# RaspBle.net
KiCad netlist of a schematic drawn in EAGLE
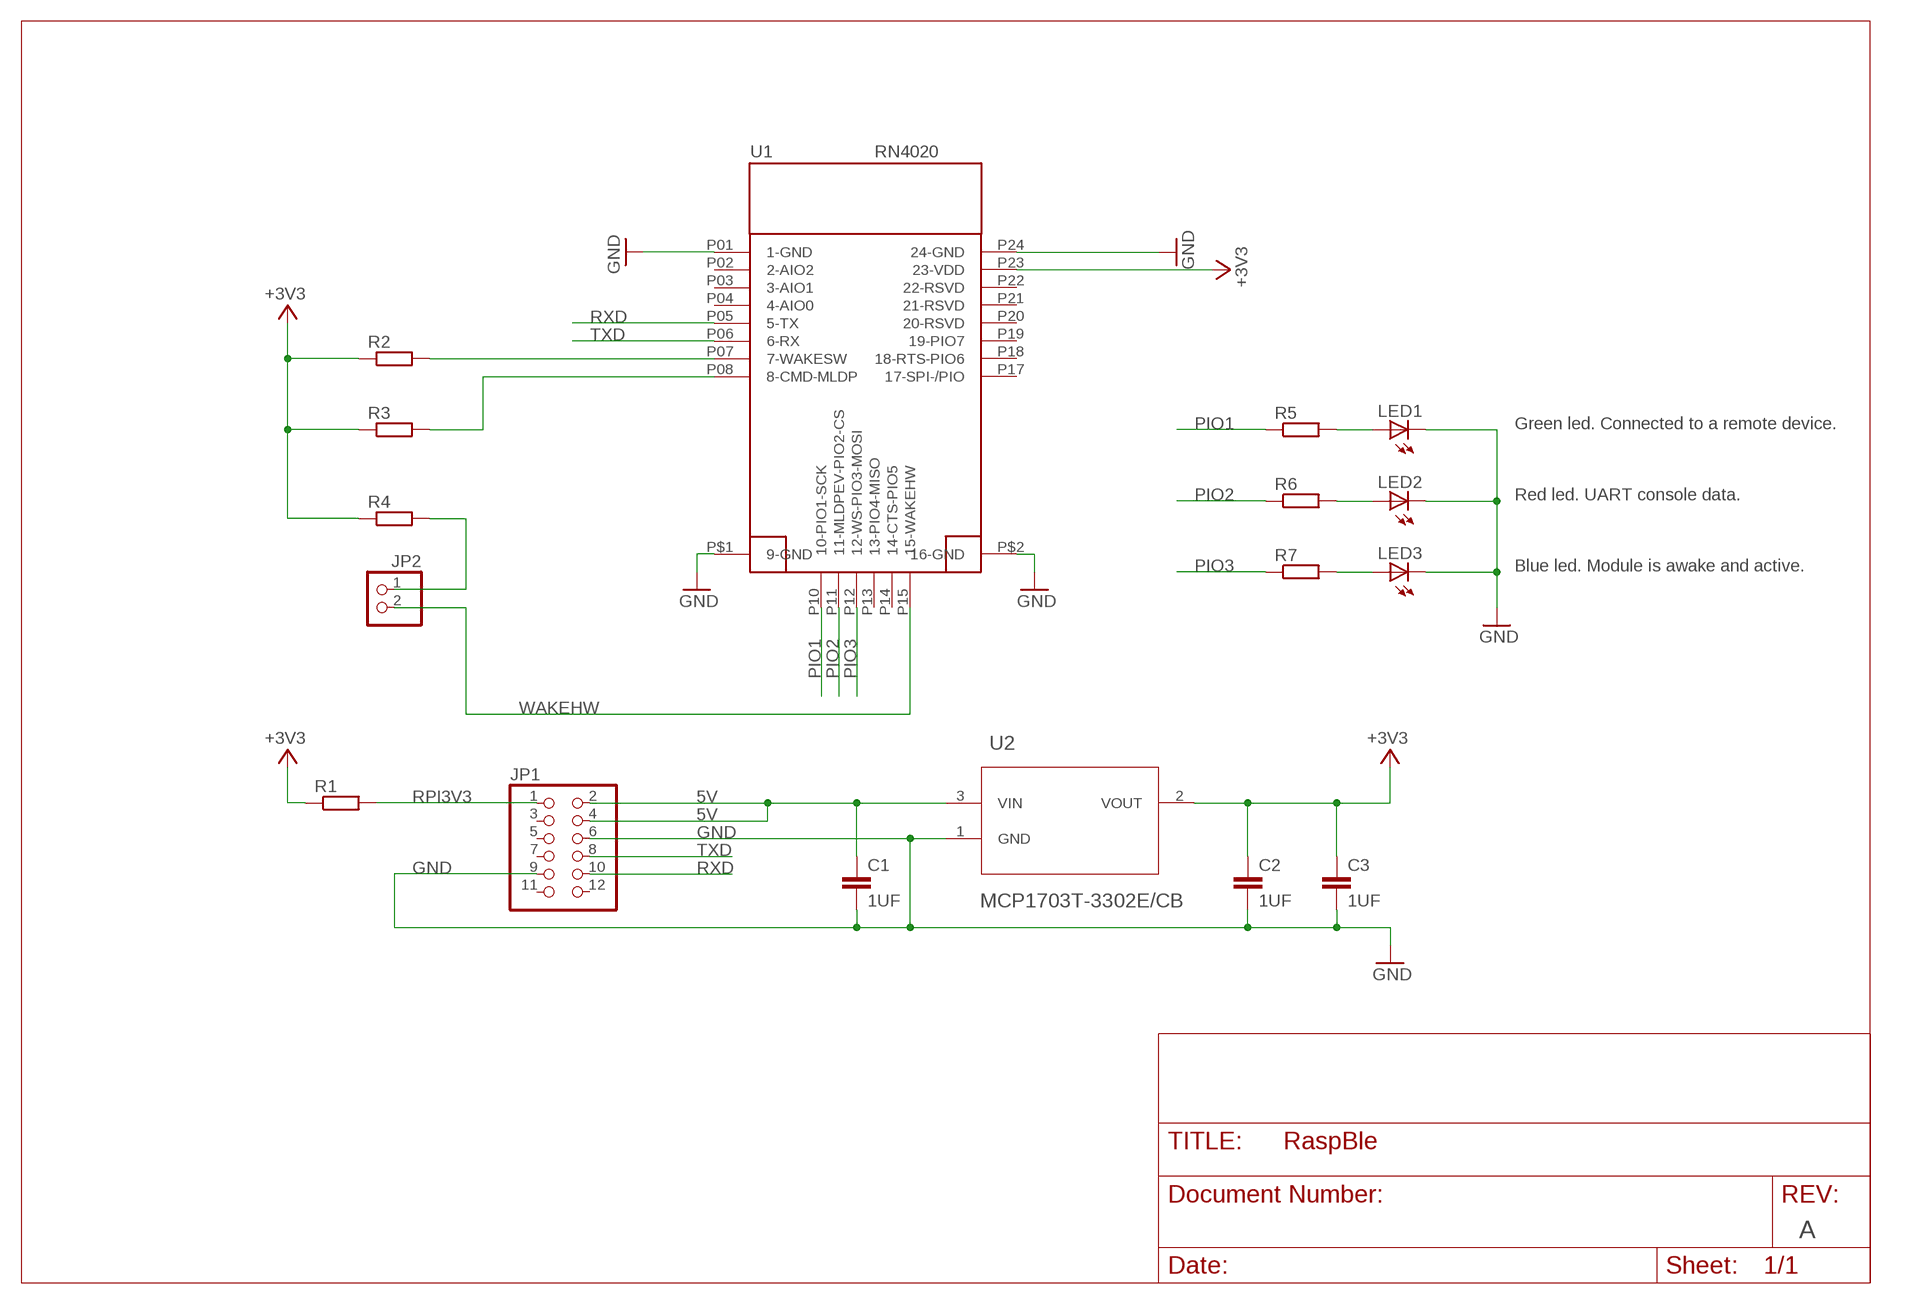
[diagram p0: schematic, sheet 1]

(export (version "E")
  (design (tool "Eeschema 10.0.6"))
  (components
    (comp (ref "C1")
      (value "1UF")
      (footprint "eagle-import:C1206")
      (libsource (lib "eagle-import") (part "C-EUC1206"))
    )
    (comp (ref "C2")
      (value "1UF")
      (footprint "eagle-import:C1206")
      (libsource (lib "eagle-import") (part "C-EUC1206"))
    )
    (comp (ref "C3")
      (value "1UF")
      (footprint "eagle-import:C1206")
      (libsource (lib "eagle-import") (part "C-EUC1206"))
    )
    (comp (ref "JP1")
      (value "PINHD-2X6")
      (footprint "eagle-import:2X06")
      (libsource (lib "eagle-import") (part "PINHD-2X6"))
    )
    (comp (ref "JP2")
      (value "PINHD-1X2")
      (footprint "eagle-import:1X02")
      (libsource (lib "eagle-import") (part "PINHD-1X2"))
    )
    (comp (ref "LED1")
      (value "LEDSML1206")
      (footprint "eagle-import:SML1206")
      (libsource (lib "eagle-import") (part "LEDSML1206"))
    )
    (comp (ref "LED2")
      (value "LEDSML1206")
      (footprint "eagle-import:SML1206")
      (libsource (lib "eagle-import") (part "LEDSML1206"))
    )
    (comp (ref "LED3")
      (value "LEDSML1206")
      (footprint "eagle-import:SML1206")
      (libsource (lib "eagle-import") (part "LEDSML1206"))
    )
    (comp (ref "R1")
      (value "R-EU_R1206")
      (footprint "eagle-import:R1206")
      (libsource (lib "eagle-import") (part "R-EU_R1206"))
    )
    (comp (ref "R2")
      (value "R-EU_R1206")
      (footprint "eagle-import:R1206")
      (libsource (lib "eagle-import") (part "R-EU_R1206"))
    )
    (comp (ref "R3")
      (value "R-EU_R1206")
      (footprint "eagle-import:R1206")
      (libsource (lib "eagle-import") (part "R-EU_R1206"))
    )
    (comp (ref "R4")
      (value "R-EU_R1206")
      (footprint "eagle-import:R1206")
      (libsource (lib "eagle-import") (part "R-EU_R1206"))
    )
    (comp (ref "R5")
      (value "R-EU_R1206")
      (footprint "eagle-import:R1206")
      (libsource (lib "eagle-import") (part "R-EU_R1206"))
    )
    (comp (ref "R6")
      (value "R-EU_R1206")
      (footprint "eagle-import:R1206")
      (libsource (lib "eagle-import") (part "R-EU_R1206"))
    )
    (comp (ref "R7")
      (value "R-EU_R1206")
      (footprint "eagle-import:R1206")
      (libsource (lib "eagle-import") (part "R-EU_R1206"))
    )
    (comp (ref "U1")
      (value "RN4020")
      (footprint "eagle-import:RN4020SMD")
      (libsource (lib "eagle-import") (part "RN4020"))
    )
    (comp (ref "U2")
      (value "MCP1703T-3302E/CB")
      (footprint "eagle-import:SOT95P300X145-3N")
      (libsource (lib "eagle-import") (part "MCP1703T-3302E/CB"))
    )
  )
  (nets
    (net (code "1") (name "+3V3") (class "Default")
      (node (ref "C2") (pin "1") (pinfunction "1_1") (pintype "passive"))
      (node (ref "C3") (pin "1") (pinfunction "1_1") (pintype "passive"))
      (node (ref "R1") (pin "1") (pinfunction "1_1") (pintype "passive"))
      (node (ref "R2") (pin "1") (pinfunction "1_1") (pintype "passive"))
      (node (ref "R3") (pin "1") (pinfunction "1_1") (pintype "passive"))
      (node (ref "R4") (pin "1") (pinfunction "1_1") (pintype "passive"))
      (node (ref "U1") (pin "P23") (pinfunction "23-VDD_P23") (pintype "bidirectional"))
      (node (ref "U2") (pin "2") (pinfunction "VOUT_2") (pintype "output"))
    )
    (net (code "2") (name "/5V") (class "Default")
      (node (ref "C1") (pin "1") (pinfunction "1_1") (pintype "passive"))
      (node (ref "JP1") (pin "2") (pinfunction "2_2") (pintype "passive"))
      (node (ref "JP1") (pin "4") (pinfunction "4_4") (pintype "passive"))
      (node (ref "U2") (pin "3") (pinfunction "VIN_3") (pintype "input"))
    )
    (net (code "3") (name "/PIO1") (class "Default")
      (node (ref "R5") (pin "1") (pinfunction "1_1") (pintype "passive"))
      (node (ref "U1") (pin "P10") (pinfunction "10-PIO1-SCK_P10") (pintype "bidirectional"))
    )
    (net (code "4") (name "/PIO2") (class "Default")
      (node (ref "R6") (pin "1") (pinfunction "1_1") (pintype "passive"))
      (node (ref "U1") (pin "P11") (pinfunction "11-MLDPEV-PIO2-CS_P11") (pintype "bidirectional"))
    )
    (net (code "5") (name "/PIO3") (class "Default")
      (node (ref "R7") (pin "1") (pinfunction "1_1") (pintype "passive"))
      (node (ref "U1") (pin "P12") (pinfunction "12-WS-PIO3-MOSI_P12") (pintype "bidirectional"))
    )
    (net (code "6") (name "/RPI3V3") (class "Default")
      (node (ref "JP1") (pin "1") (pinfunction "1_1") (pintype "passive"))
      (node (ref "R1") (pin "2") (pinfunction "2_2") (pintype "passive"))
    )
    (net (code "7") (name "/RXD") (class "Default")
      (node (ref "JP1") (pin "10") (pinfunction "10_10") (pintype "passive"))
      (node (ref "U1") (pin "P05") (pinfunction "5-TX_P05") (pintype "bidirectional"))
    )
    (net (code "8") (name "/TXD") (class "Default")
      (node (ref "JP1") (pin "8") (pinfunction "8_8") (pintype "passive"))
      (node (ref "U1") (pin "P06") (pinfunction "6-RX_P06") (pintype "bidirectional"))
    )
    (net (code "9") (name "/WAKEHW") (class "Default")
      (node (ref "JP2") (pin "2") (pinfunction "2_2") (pintype "passive"))
      (node (ref "U1") (pin "P15") (pinfunction "15-WAKEHW_P15") (pintype "bidirectional"))
    )
    (net (code "10") (name "GND") (class "Default")
      (node (ref "C1") (pin "2") (pinfunction "2_2") (pintype "passive"))
      (node (ref "C2") (pin "2") (pinfunction "2_2") (pintype "passive"))
      (node (ref "C3") (pin "2") (pinfunction "2_2") (pintype "passive"))
      (node (ref "JP1") (pin "6") (pinfunction "6_6") (pintype "passive"))
      (node (ref "JP1") (pin "9") (pinfunction "9_9") (pintype "passive"))
      (node (ref "LED1") (pin "C") (pinfunction "C_C") (pintype "passive"))
      (node (ref "LED2") (pin "C") (pinfunction "C_C") (pintype "passive"))
      (node (ref "LED3") (pin "C") (pinfunction "C_C") (pintype "passive"))
      (node (ref "U1") (pin "P$1") (pinfunction "9-GND_P$1") (pintype "bidirectional"))
      (node (ref "U1") (pin "P$2") (pinfunction "16-GND_P$2") (pintype "bidirectional"))
      (node (ref "U1") (pin "P01") (pinfunction "1-GND_P01") (pintype "bidirectional"))
      (node (ref "U1") (pin "P24") (pinfunction "24-GND_P24") (pintype "bidirectional"))
      (node (ref "U2") (pin "1") (pinfunction "GND_1") (pintype "passive"))
    )
    (net (code "11") (name "Net-(JP2-Pad1)") (class "Default")
      (node (ref "JP2") (pin "1") (pinfunction "1_1") (pintype "passive"))
      (node (ref "R4") (pin "2") (pinfunction "2_2") (pintype "passive"))
    )
    (net (code "12") (name "Net-(LED1-PadA)") (class "Default")
      (node (ref "LED1") (pin "A") (pinfunction "A_A") (pintype "passive"))
      (node (ref "R5") (pin "2") (pinfunction "2_2") (pintype "passive"))
    )
    (net (code "13") (name "Net-(LED2-PadA)") (class "Default")
      (node (ref "LED2") (pin "A") (pinfunction "A_A") (pintype "passive"))
      (node (ref "R6") (pin "2") (pinfunction "2_2") (pintype "passive"))
    )
    (net (code "14") (name "Net-(LED3-PadA)") (class "Default")
      (node (ref "LED3") (pin "A") (pinfunction "A_A") (pintype "passive"))
      (node (ref "R7") (pin "2") (pinfunction "2_2") (pintype "passive"))
    )
    (net (code "15") (name "Net-(U1-7-WAKESW)") (class "Default")
      (node (ref "R2") (pin "2") (pinfunction "2_2") (pintype "passive"))
      (node (ref "U1") (pin "P07") (pinfunction "7-WAKESW_P07") (pintype "bidirectional"))
    )
    (net (code "16") (name "Net-(U1-8-CMD-MLDP)") (class "Default")
      (node (ref "R3") (pin "2") (pinfunction "2_2") (pintype "passive"))
      (node (ref "U1") (pin "P08") (pinfunction "8-CMD-MLDP_P08") (pintype "bidirectional"))
    )
    (net (code "17") (name "unconnected-(JP1-Pad3)") (class "Default")
      (node (ref "JP1") (pin "3") (pinfunction "3_3") (pintype "passive"))
    )
    (net (code "18") (name "unconnected-(JP1-Pad5)") (class "Default")
      (node (ref "JP1") (pin "5") (pinfunction "5_5") (pintype "passive"))
    )
    (net (code "19") (name "unconnected-(JP1-Pad7)") (class "Default")
      (node (ref "JP1") (pin "7") (pinfunction "7_7") (pintype "passive"))
    )
    (net (code "20") (name "unconnected-(JP1-Pad11)") (class "Default")
      (node (ref "JP1") (pin "11") (pinfunction "11_11") (pintype "passive"))
    )
    (net (code "21") (name "unconnected-(JP1-Pad12)") (class "Default")
      (node (ref "JP1") (pin "12") (pinfunction "12_12") (pintype "passive"))
    )
    (net (code "22") (name "unconnected-(U1-2-AIO2-PadP02)") (class "Default")
      (node (ref "U1") (pin "P02") (pinfunction "2-AIO2_P02") (pintype "bidirectional"))
    )
    (net (code "23") (name "unconnected-(U1-3-AIO1-PadP03)") (class "Default")
      (node (ref "U1") (pin "P03") (pinfunction "3-AIO1_P03") (pintype "bidirectional"))
    )
    (net (code "24") (name "unconnected-(U1-4-AIO0-PadP04)") (class "Default")
      (node (ref "U1") (pin "P04") (pinfunction "4-AIO0_P04") (pintype "bidirectional"))
    )
    (net (code "25") (name "unconnected-(U1-13-PIO4-MISO-PadP13)") (class "Default")
      (node (ref "U1") (pin "P13") (pinfunction "13-PIO4-MISO_P13") (pintype "bidirectional"))
    )
    (net (code "26") (name "unconnected-(U1-14-CTS-PIO5-PadP14)") (class "Default")
      (node (ref "U1") (pin "P14") (pinfunction "14-CTS-PIO5_P14") (pintype "bidirectional"))
    )
    (net (code "27") (name "unconnected-(U1-17-SPI-{slash}PIO-PadP17)") (class "Default")
      (node (ref "U1") (pin "P17") (pinfunction "17-SPI-/PIO_P17") (pintype "bidirectional"))
    )
    (net (code "28") (name "unconnected-(U1-18-RTS-PIO6-PadP18)") (class "Default")
      (node (ref "U1") (pin "P18") (pinfunction "18-RTS-PIO6_P18") (pintype "bidirectional"))
    )
    (net (code "29") (name "unconnected-(U1-19-PIO7-PadP19)") (class "Default")
      (node (ref "U1") (pin "P19") (pinfunction "19-PIO7_P19") (pintype "bidirectional"))
    )
    (net (code "30") (name "unconnected-(U1-20-RSVD-PadP20)") (class "Default")
      (node (ref "U1") (pin "P20") (pinfunction "20-RSVD_P20") (pintype "bidirectional"))
    )
    (net (code "31") (name "unconnected-(U1-21-RSVD-PadP21)") (class "Default")
      (node (ref "U1") (pin "P21") (pinfunction "21-RSVD_P21") (pintype "bidirectional"))
    )
    (net (code "32") (name "unconnected-(U1-22-RSVD-PadP22)") (class "Default")
      (node (ref "U1") (pin "P22") (pinfunction "22-RSVD_P22") (pintype "bidirectional"))
    )
  )
)
